# mj-2506n_daughterboard.net
KiCad netlist of a schematic drawn in EAGLE
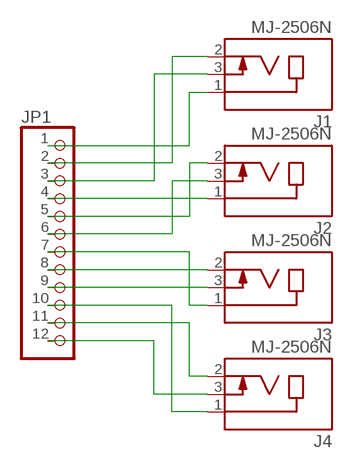
[diagram p0: schematic, sheet 1]

(export (version "E")
  (design (tool "Eeschema 10.0.6"))
  (components
    (comp (ref "J1")
      (value "MJ-2506N")
      (footprint "eagle-import:CUI_MJ-2506N")
      (fields (field (name "MANUFACTURER") "CUI INC"))
      (libsource (lib "eagle-import") (part "MJ-2506N"))
    )
    (comp (ref "J2")
      (value "MJ-2506N")
      (footprint "eagle-import:CUI_MJ-2506N")
      (fields (field (name "MANUFACTURER") "CUI INC"))
      (libsource (lib "eagle-import") (part "MJ-2506N"))
    )
    (comp (ref "J3")
      (value "MJ-2506N")
      (footprint "eagle-import:CUI_MJ-2506N")
      (fields (field (name "MANUFACTURER") "CUI INC"))
      (libsource (lib "eagle-import") (part "MJ-2506N"))
    )
    (comp (ref "J4")
      (value "MJ-2506N")
      (footprint "eagle-import:CUI_MJ-2506N")
      (fields (field (name "MANUFACTURER") "CUI INC"))
      (libsource (lib "eagle-import") (part "MJ-2506N"))
    )
    (comp (ref "JP1")
      (value "PINHD-1X12")
      (footprint "eagle-import:1X12")
      (libsource (lib "eagle-import") (part "PINHD-1X12"))
    )
  )
  (nets
    (net (code "1") (name "Net-(J1-Pad1)") (class "Default")
      (node (ref "J1") (pin "1") (pinfunction "1_1") (pintype "passive"))
      (node (ref "JP1") (pin "1") (pinfunction "1_1") (pintype "passive"))
    )
    (net (code "2") (name "Net-(J1-Pad2)") (class "Default")
      (node (ref "J1") (pin "2") (pinfunction "2_2") (pintype "passive"))
      (node (ref "JP1") (pin "2") (pinfunction "2_2") (pintype "passive"))
    )
    (net (code "3") (name "Net-(J1-Pad3)") (class "Default")
      (node (ref "J1") (pin "3") (pinfunction "3_3") (pintype "passive"))
      (node (ref "JP1") (pin "3") (pinfunction "3_3") (pintype "passive"))
    )
    (net (code "4") (name "Net-(J2-Pad1)") (class "Default")
      (node (ref "J2") (pin "1") (pinfunction "1_1") (pintype "passive"))
      (node (ref "JP1") (pin "4") (pinfunction "4_4") (pintype "passive"))
    )
    (net (code "5") (name "Net-(J2-Pad2)") (class "Default")
      (node (ref "J2") (pin "2") (pinfunction "2_2") (pintype "passive"))
      (node (ref "JP1") (pin "5") (pinfunction "5_5") (pintype "passive"))
    )
    (net (code "6") (name "Net-(J2-Pad3)") (class "Default")
      (node (ref "J2") (pin "3") (pinfunction "3_3") (pintype "passive"))
      (node (ref "JP1") (pin "6") (pinfunction "6_6") (pintype "passive"))
    )
    (net (code "7") (name "Net-(J3-Pad1)") (class "Default")
      (node (ref "J3") (pin "1") (pinfunction "1_1") (pintype "passive"))
      (node (ref "JP1") (pin "7") (pinfunction "7_7") (pintype "passive"))
    )
    (net (code "8") (name "Net-(J3-Pad2)") (class "Default")
      (node (ref "J3") (pin "2") (pinfunction "2_2") (pintype "passive"))
      (node (ref "JP1") (pin "8") (pinfunction "8_8") (pintype "passive"))
    )
    (net (code "9") (name "Net-(J3-Pad3)") (class "Default")
      (node (ref "J3") (pin "3") (pinfunction "3_3") (pintype "passive"))
      (node (ref "JP1") (pin "9") (pinfunction "9_9") (pintype "passive"))
    )
    (net (code "10") (name "Net-(J4-Pad1)") (class "Default")
      (node (ref "J4") (pin "1") (pinfunction "1_1") (pintype "passive"))
      (node (ref "JP1") (pin "10") (pinfunction "10_10") (pintype "passive"))
    )
    (net (code "11") (name "Net-(J4-Pad2)") (class "Default")
      (node (ref "J4") (pin "2") (pinfunction "2_2") (pintype "passive"))
      (node (ref "JP1") (pin "11") (pinfunction "11_11") (pintype "passive"))
    )
    (net (code "12") (name "Net-(J4-Pad3)") (class "Default")
      (node (ref "J4") (pin "3") (pinfunction "3_3") (pintype "passive"))
      (node (ref "JP1") (pin "12") (pinfunction "12_12") (pintype "passive"))
    )
  )
)
